# Self_Designed_Schematic.net
KiCad netlist of a schematic drawn in EAGLE
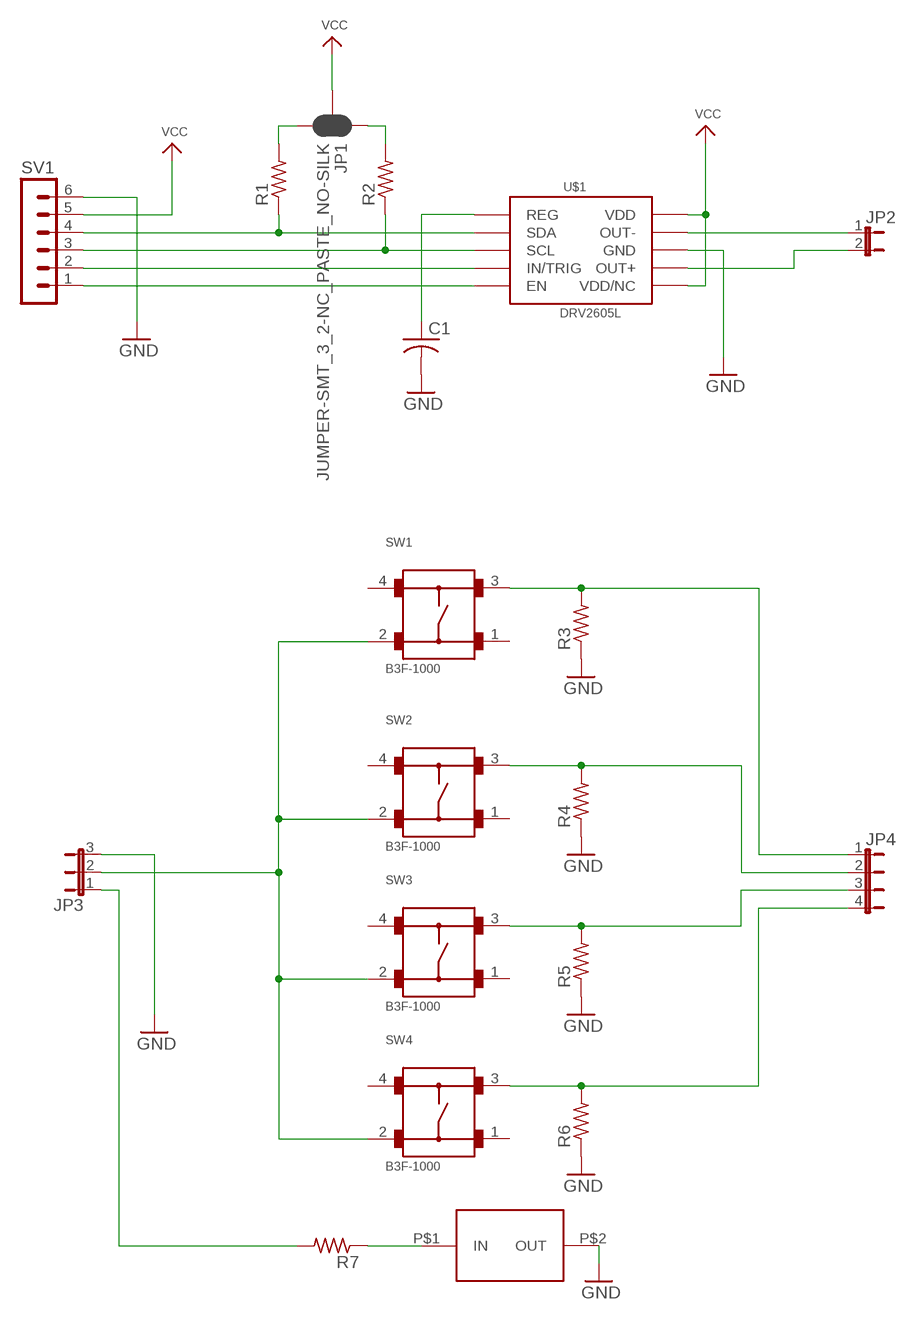
[diagram p0: schematic, sheet 1]

(export (version "E")
  (design (tool "Eeschema 10.0.6"))
  (components
    (comp (ref "C1")
      (value "C-USC0402")
      (footprint "eagle-import:C0402")
      (libsource (lib "eagle-import") (part "C-USC0402"))
    )
    (comp (ref "JP1")
      (value "JUMPER-SMT_3_2-NC_PASTE_NO-SILK")
      (footprint "eagle-import:SMT-JUMPER_3_2-NC_PASTE_NO-SILK")
      (libsource (lib "eagle-import") (part "JUMPER-SMT_3_2-NC_PASTE_NO-SILK"))
    )
    (comp (ref "JP2")
      (value "JP1E")
      (footprint "eagle-import:JP1")
      (libsource (lib "eagle-import") (part "JP1E"))
    )
    (comp (ref "JP3")
      (value "JP2W")
      (footprint "eagle-import:JP2W")
      (libsource (lib "eagle-import") (part "JP2W"))
    )
    (comp (ref "JP4")
      (value "JP4E")
      (footprint "eagle-import:JP4")
      (libsource (lib "eagle-import") (part "JP4E"))
    )
    (comp (ref "R1")
      (value "R-US_M0805")
      (footprint "eagle-import:M0805")
      (libsource (lib "eagle-import") (part "R-US_M0805"))
    )
    (comp (ref "R2")
      (value "R-US_M0805")
      (footprint "eagle-import:M0805")
      (libsource (lib "eagle-import") (part "R-US_M0805"))
    )
    (comp (ref "R3")
      (value "R-US_M0805")
      (footprint "eagle-import:M0805")
      (libsource (lib "eagle-import") (part "R-US_M0805"))
    )
    (comp (ref "R4")
      (value "R-US_M0805")
      (footprint "eagle-import:M0805")
      (libsource (lib "eagle-import") (part "R-US_M0805"))
    )
    (comp (ref "R5")
      (value "R-US_M0805")
      (footprint "eagle-import:M0805")
      (libsource (lib "eagle-import") (part "R-US_M0805"))
    )
    (comp (ref "R6")
      (value "R-US_M0805")
      (footprint "eagle-import:M0805")
      (libsource (lib "eagle-import") (part "R-US_M0805"))
    )
    (comp (ref "R7")
      (value "R-US_M0805")
      (footprint "eagle-import:M0805")
      (libsource (lib "eagle-import") (part "R-US_M0805"))
    )
    (comp (ref "SV1")
      (value "MA06-1")
      (footprint "eagle-import:MA06-1")
      (libsource (lib "eagle-import") (part "MA06-1"))
    )
    (comp (ref "SW1")
      (value "B3F-1000")
      (footprint "eagle-import:B3F-1000")
      (fields
        (field (name "DIGI_KEY_PART_NUMBER") "SW400-ND")
        (field (name "MANUFACTURER") "Omron Electronics Inc-EMC Div")
        (field (name "CREATED_BY") "PCBLayout.com")
      )
      (libsource (lib "eagle-import") (part "B3F-1000"))
    )
    (comp (ref "SW2")
      (value "B3F-1000")
      (footprint "eagle-import:B3F-1000")
      (fields
        (field (name "DIGI_KEY_PART_NUMBER") "SW400-ND")
        (field (name "MANUFACTURER") "Omron Electronics Inc-EMC Div")
        (field (name "CREATED_BY") "PCBLayout.com")
      )
      (libsource (lib "eagle-import") (part "B3F-1000"))
    )
    (comp (ref "SW3")
      (value "B3F-1000")
      (footprint "eagle-import:B3F-1000")
      (fields
        (field (name "DIGI_KEY_PART_NUMBER") "SW400-ND")
        (field (name "MANUFACTURER") "Omron Electronics Inc-EMC Div")
        (field (name "CREATED_BY") "PCBLayout.com")
      )
      (libsource (lib "eagle-import") (part "B3F-1000"))
    )
    (comp (ref "SW4")
      (value "B3F-1000")
      (footprint "eagle-import:B3F-1000")
      (fields
        (field (name "DIGI_KEY_PART_NUMBER") "SW400-ND")
        (field (name "MANUFACTURER") "Omron Electronics Inc-EMC Div")
        (field (name "CREATED_BY") "PCBLayout.com")
      )
      (libsource (lib "eagle-import") (part "B3F-1000"))
    )
    (comp (ref "U$1")
      (value "DRV2605L")
      (footprint "eagle-import:VSSOP-10")
      (libsource (lib "eagle-import") (part "DRV2605L"))
    )
    (comp (ref "U$2")
      (value "PIEZOBUZZER")
      (footprint "eagle-import:PIEZOBUZZER")
      (libsource (lib "eagle-import") (part "PIEZOBUZZER"))
    )
  )
  (nets
    (net (code "1") (name "GND") (class "Default")
      (node (ref "C1") (pin "2") (pinfunction "2_2") (pintype "passive"))
      (node (ref "JP3") (pin "3") (pinfunction "3_3") (pintype "passive"))
      (node (ref "R3") (pin "1") (pinfunction "1_1") (pintype "passive"))
      (node (ref "R4") (pin "1") (pinfunction "1_1") (pintype "passive"))
      (node (ref "R5") (pin "1") (pinfunction "1_1") (pintype "passive"))
      (node (ref "R6") (pin "1") (pinfunction "1_1") (pintype "passive"))
      (node (ref "SV1") (pin "6") (pinfunction "6_6") (pintype "passive"))
      (node (ref "U$1") (pin "P$8") (pinfunction "GND_P$8") (pintype "bidirectional"))
      (node (ref "U$2") (pin "P$2") (pinfunction "OUT_P$2") (pintype "bidirectional"))
    )
    (net (code "2") (name "Net-(JP1-Pad1)") (class "Default")
      (node (ref "JP1") (pin "1") (pinfunction "1_1") (pintype "passive"))
      (node (ref "R2") (pin "2") (pinfunction "2_2") (pintype "passive"))
    )
    (net (code "3") (name "Net-(JP1-Pad3)") (class "Default")
      (node (ref "JP1") (pin "3") (pinfunction "3_3") (pintype "passive"))
      (node (ref "R1") (pin "2") (pinfunction "2_2") (pintype "passive"))
    )
    (net (code "4") (name "Net-(JP3-Pad1)") (class "Default")
      (node (ref "JP3") (pin "1") (pinfunction "1_1") (pintype "passive"))
      (node (ref "R7") (pin "2") (pinfunction "2_2") (pintype "passive"))
    )
    (net (code "5") (name "Net-(JP3-Pad2)") (class "Default")
      (node (ref "JP3") (pin "2") (pinfunction "2_2") (pintype "passive"))
      (node (ref "SW1") (pin "2") (pinfunction "2_2") (pintype "passive"))
      (node (ref "SW2") (pin "2") (pinfunction "2_2") (pintype "passive"))
      (node (ref "SW3") (pin "2") (pinfunction "2_2") (pintype "passive"))
      (node (ref "SW4") (pin "2") (pinfunction "2_2") (pintype "passive"))
    )
    (net (code "6") (name "Net-(JP4-Pad1)") (class "Default")
      (node (ref "JP4") (pin "1") (pinfunction "1_1") (pintype "passive"))
      (node (ref "R3") (pin "2") (pinfunction "2_2") (pintype "passive"))
      (node (ref "SW1") (pin "3") (pinfunction "3_3") (pintype "passive"))
    )
    (net (code "7") (name "Net-(JP4-Pad2)") (class "Default")
      (node (ref "JP4") (pin "2") (pinfunction "2_2") (pintype "passive"))
      (node (ref "R4") (pin "2") (pinfunction "2_2") (pintype "passive"))
      (node (ref "SW2") (pin "3") (pinfunction "3_3") (pintype "passive"))
    )
    (net (code "8") (name "Net-(JP4-Pad3)") (class "Default")
      (node (ref "JP4") (pin "3") (pinfunction "3_3") (pintype "passive"))
      (node (ref "R5") (pin "2") (pinfunction "2_2") (pintype "passive"))
      (node (ref "SW3") (pin "3") (pinfunction "3_3") (pintype "passive"))
    )
    (net (code "9") (name "Net-(JP4-Pad4)") (class "Default")
      (node (ref "JP4") (pin "4") (pinfunction "4_4") (pintype "passive"))
      (node (ref "R6") (pin "2") (pinfunction "2_2") (pintype "passive"))
      (node (ref "SW4") (pin "3") (pinfunction "3_3") (pintype "passive"))
    )
    (net (code "10") (name "Net-(U$1-EN)") (class "Default")
      (node (ref "SV1") (pin "1") (pinfunction "1_1") (pintype "passive"))
      (node (ref "U$1") (pin "P$5") (pinfunction "EN_P$5") (pintype "bidirectional"))
    )
    (net (code "11") (name "Net-(U$1-IN{slash}TRIG)") (class "Default")
      (node (ref "SV1") (pin "2") (pinfunction "2_2") (pintype "passive"))
      (node (ref "U$1") (pin "P$4") (pinfunction "IN/TRIG_P$4") (pintype "bidirectional"))
    )
    (net (code "12") (name "Net-(U$1-OUT+)") (class "Default")
      (node (ref "JP2") (pin "2") (pinfunction "2_2") (pintype "passive"))
      (node (ref "U$1") (pin "P$7") (pinfunction "OUT+_P$7") (pintype "bidirectional"))
    )
    (net (code "13") (name "Net-(U$1-OUT-)") (class "Default")
      (node (ref "JP2") (pin "1") (pinfunction "1_1") (pintype "passive"))
      (node (ref "U$1") (pin "P$9") (pinfunction "OUT-_P$9") (pintype "bidirectional"))
    )
    (net (code "14") (name "Net-(U$1-REG)") (class "Default")
      (node (ref "C1") (pin "1") (pinfunction "1_1") (pintype "passive"))
      (node (ref "U$1") (pin "P$1") (pinfunction "REG_P$1") (pintype "bidirectional"))
    )
    (net (code "15") (name "Net-(U$1-SCL)") (class "Default")
      (node (ref "R2") (pin "1") (pinfunction "1_1") (pintype "passive"))
      (node (ref "SV1") (pin "3") (pinfunction "3_3") (pintype "passive"))
      (node (ref "U$1") (pin "P$2") (pinfunction "SCL_P$2") (pintype "bidirectional"))
    )
    (net (code "16") (name "Net-(U$1-SDA)") (class "Default")
      (node (ref "R1") (pin "1") (pinfunction "1_1") (pintype "passive"))
      (node (ref "SV1") (pin "4") (pinfunction "4_4") (pintype "passive"))
      (node (ref "U$1") (pin "P$3") (pinfunction "SDA_P$3") (pintype "bidirectional"))
    )
    (net (code "17") (name "Net-(U$2-IN)") (class "Default")
      (node (ref "R7") (pin "1") (pinfunction "1_1") (pintype "passive"))
      (node (ref "U$2") (pin "P$1") (pinfunction "IN_P$1") (pintype "bidirectional"))
    )
    (net (code "18") (name "VCC") (class "Default")
      (node (ref "JP1") (pin "2") (pinfunction "2_2") (pintype "passive"))
      (node (ref "SV1") (pin "5") (pinfunction "5_5") (pintype "passive"))
      (node (ref "U$1") (pin "P$10") (pinfunction "VDD_P$10") (pintype "bidirectional"))
      (node (ref "U$1") (pin "P$6") (pinfunction "VDD/NC_P$6") (pintype "bidirectional"))
    )
    (net (code "19") (name "unconnected-(SW1-Pad1)") (class "Default")
      (node (ref "SW1") (pin "1") (pinfunction "1_1") (pintype "passive"))
    )
    (net (code "20") (name "unconnected-(SW1-Pad4)") (class "Default")
      (node (ref "SW1") (pin "4") (pinfunction "4_4") (pintype "passive"))
    )
    (net (code "21") (name "unconnected-(SW2-Pad1)") (class "Default")
      (node (ref "SW2") (pin "1") (pinfunction "1_1") (pintype "passive"))
    )
    (net (code "22") (name "unconnected-(SW2-Pad4)") (class "Default")
      (node (ref "SW2") (pin "4") (pinfunction "4_4") (pintype "passive"))
    )
    (net (code "23") (name "unconnected-(SW3-Pad1)") (class "Default")
      (node (ref "SW3") (pin "1") (pinfunction "1_1") (pintype "passive"))
    )
    (net (code "24") (name "unconnected-(SW3-Pad4)") (class "Default")
      (node (ref "SW3") (pin "4") (pinfunction "4_4") (pintype "passive"))
    )
    (net (code "25") (name "unconnected-(SW4-Pad1)") (class "Default")
      (node (ref "SW4") (pin "1") (pinfunction "1_1") (pintype "passive"))
    )
    (net (code "26") (name "unconnected-(SW4-Pad4)") (class "Default")
      (node (ref "SW4") (pin "4") (pinfunction "4_4") (pintype "passive"))
    )
  )
)
